# SCH_Stimulus-Shield-_GroeiAcademie-Frame.net
KiCad netlist of a schematic drawn in EasyEDA
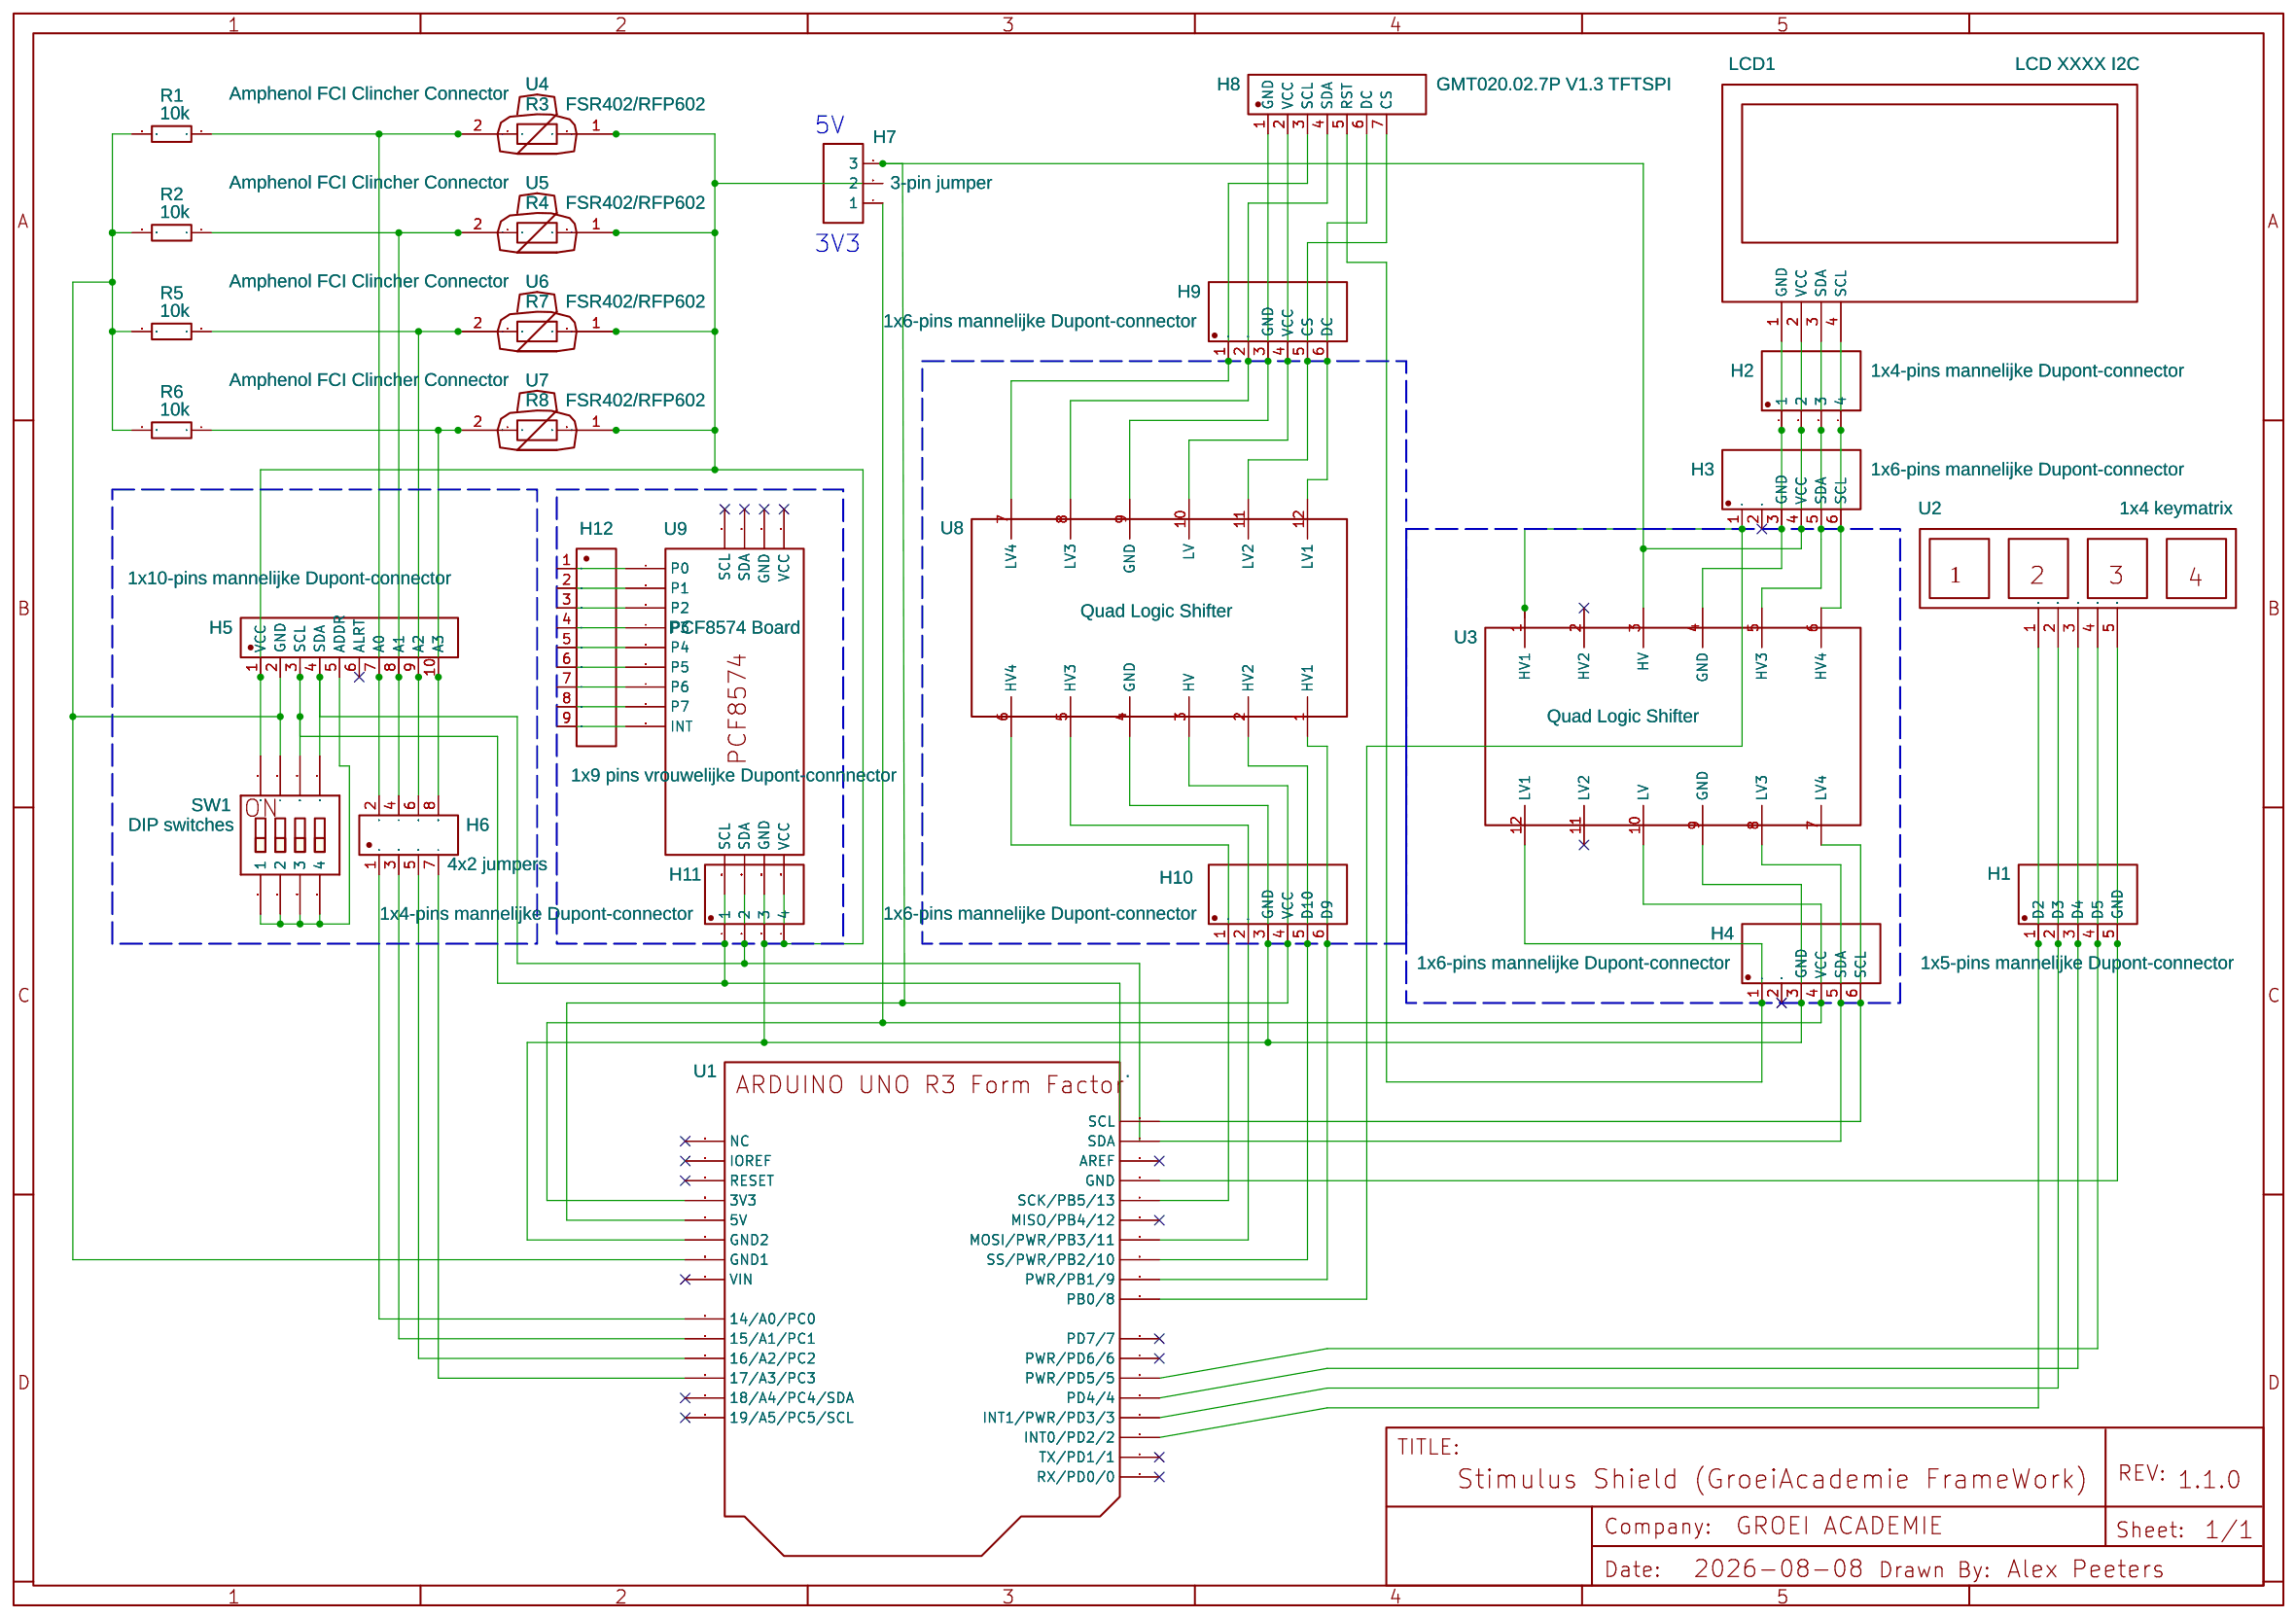
[diagram p0: schematic sheet]

(export (version "E")
  (design (tool "Eeschema 10.0.6"))
  (components
    (comp (ref "H1")
      (value "1x5-pins mannelijke Dupont-connector")
      (fields (field (name "Manufacturer Part") "B-2100S05P-A110") (field (name "Manufacturer") "Ckmtw(灿科盟)"))
      (libsource (lib "") (part "210S-1*5P L=11.6MMGold-plated black"))
    )
    (comp (ref "H2")
      (value "1x4-pins mannelijke Dupont-connector")
      (fields (field (name "Manufacturer Part") "B-2100S04P-A110") (field (name "Manufacturer") "Ckmtw(灿科盟)"))
      (libsource (lib "") (part "Header-Male-2.54_1x4"))
    )
    (comp (ref "H3")
      (value "1x6-pins mannelijke Dupont-connector")
      (fields (field (name "Manufacturer Part") "B-2100S06P-A110") (field (name "Manufacturer") "Ckmtw(灿科盟)"))
      (libsource (lib "") (part "210S-1*6P L=11.6MMGold-plated black"))
    )
    (comp (ref "H4")
      (value "1x6-pins mannelijke Dupont-connector")
      (fields (field (name "Manufacturer Part") "B-2100S06P-A110") (field (name "Manufacturer") "Ckmtw(灿科盟)"))
      (libsource (lib "") (part "210S-1*6P L=11.6MMGold-plated black"))
    )
    (comp (ref "H5")
      (value "1x10-pins mannelijke Dupont-connector")
      (fields (field (name "Manufacturer Part") "2.54-1*10") (field (name "Manufacturer") "ZHOURI(洲日)"))
      (libsource (lib "") (part "2.54-1*10"))
    )
    (comp (ref "H6")
      (value "4x2 jumpers")
      (fields (field (name "Manufacturer Part") "2.54-2*4P立贴针") (field (name "Manufacturer") "BOOMELE(博穆精密)"))
      (libsource (lib "") (part "2.54-2*4P立贴针"))
    )
    (comp (ref "H7") (value "3-pin jumper") (libsource (lib "") (part "HDR-F-2.54_1x3")))
    (comp (ref "H8")
      (value "GMT020.02.7P V1.3 TFTSPI")
      (fields (field (name "Manufacturer Part") "HDR-M-L12-3+4-1x8P-2.54"))
      (libsource (lib "") (part "PZ254R-11-08P"))
    )
    (comp (ref "H9")
      (value "1x6-pins mannelijke Dupont-connector")
      (fields (field (name "Manufacturer Part") "B-2100S06P-A110") (field (name "Manufacturer") "Ckmtw(灿科盟)"))
      (libsource (lib "") (part "210S-1*6P L=11.6MMGold-plated black_2"))
    )
    (comp (ref "H10")
      (value "1x6-pins mannelijke Dupont-connector")
      (fields (field (name "Manufacturer Part") "B-2100S06P-A110") (field (name "Manufacturer") "Ckmtw(灿科盟)"))
      (libsource (lib "") (part "210S-1*6P L=11.6MMGold-plated black_1"))
    )
    (comp (ref "H11")
      (value "1x4-pins mannelijke Dupont-connector")
      (fields (field (name "Manufacturer Part") "B-2100S04P-A110") (field (name "Manufacturer") "Ckmtw(灿科盟)"))
      (libsource (lib "") (part "Header-Male-2.54_1x4"))
    )
    (comp (ref "H12")
      (value "1x9 pins vrouwelijke Dupont-connnector")
      (fields
        (field (name "Manufacturer Part") "HX PM1.27-1x9P ZC H2.0")
        (field (name "Manufacturer") "hanxia(韩下)")
      )
      (libsource (lib "") (part "HX PM1.27-1X9P ZC H2.0"))
    )
    (comp (ref "LCD1") (value "LCD XXXX I2C") (libsource (lib "") (part "I2CLCD16X2_N")))
    (comp (ref "R1")
      (value "10k")
      (fields (field (name "Manufacturer") "Made in China"))
      (libsource (lib "") (part "330Ω (331) ±5%"))
    )
    (comp (ref "R2")
      (value "10k")
      (fields (field (name "Manufacturer") "Made in China"))
      (libsource (lib "") (part "330Ω (331) ±5%"))
    )
    (comp (ref "R3") (value "FSR402/RFP602") (libsource (lib "") (part "FSR402-OPCION1")))
    (comp (ref "R4") (value "FSR402/RFP602") (libsource (lib "") (part "FSR402-OPCION1")))
    (comp (ref "R5")
      (value "10k")
      (fields (field (name "Manufacturer") "Made in China"))
      (libsource (lib "") (part "330Ω (331) ±5%"))
    )
    (comp (ref "R6")
      (value "10k")
      (fields (field (name "Manufacturer") "Made in China"))
      (libsource (lib "") (part "330Ω (331) ±5%"))
    )
    (comp (ref "R7") (value "FSR402/RFP602") (libsource (lib "") (part "FSR402-OPCION1")))
    (comp (ref "R8") (value "FSR402/RFP602") (libsource (lib "") (part "FSR402-OPCION1")))
    (comp (ref "SW1")
      (value "DIP switches")
      (fields
        (field (name "Manufacturer Part") "DIP switch,Dip Switch,DSWB04LHGET")
        (field (name "Manufacturer") "KE")
      )
      (libsource (lib "") (part "DIP switch 4 Channel"))
    )
    (comp (ref "U1") (value ".") (libsource (lib "") (part "ARDUINO UNO r3")))
    (comp (ref "U2") (value "1x4 keymatrix") (libsource (lib "") (part "Клавиатура 4*4")))
    (comp (ref "U3") (value "Quad Logic Shifter") (libsource (lib "") (part "Quad Logic Shifter_1")))
    (comp (ref "U4")
      (value "Amphenol FCI Clincher Connector")
      (fields (field (name "Manufacturer Part") "AT04-2P-BM02") (field (name "Manufacturer") "Amphenol"))
      (libsource (lib "") (part "AT04-2P"))
    )
    (comp (ref "U5")
      (value "Amphenol FCI Clincher Connector")
      (fields (field (name "Manufacturer Part") "AT04-2P-BM02") (field (name "Manufacturer") "Amphenol"))
      (libsource (lib "") (part "AT04-2P"))
    )
    (comp (ref "U6")
      (value "Amphenol FCI Clincher Connector")
      (fields (field (name "Manufacturer Part") "AT04-2P-BM02") (field (name "Manufacturer") "Amphenol"))
      (libsource (lib "") (part "AT04-2P"))
    )
    (comp (ref "U7")
      (value "Amphenol FCI Clincher Connector")
      (fields (field (name "Manufacturer Part") "AT04-2P-BM02") (field (name "Manufacturer") "Amphenol"))
      (libsource (lib "") (part "AT04-2P"))
    )
    (comp (ref "U8") (value "Quad Logic Shifter") (libsource (lib "") (part "Quad Logic Shifter")))
    (comp (ref "U9")
      (value "PCF8574 Board")
      (fields
        (field (name "Manufacturer Part") "PCF8574 IO Expansion Board")
        (field (name "Manufacturer") "WaveShare")
      )
      (libsource (lib "") (part "PCF8574 IO Expansion Board"))
    )
  )
  (nets
    (net (code "1") (name "Net-(H1-D2)") (class "Default")
      (node (ref "H1") (pin "1") (pinfunction "D2_1") (pintype "unspecified"))
      (node (ref "U1") (pin "3") (pinfunction "INT0/PD2/2_3") (pintype "unspecified"))
      (node (ref "U2") (pin "1") (pinfunction "C1_1") (pintype "unspecified"))
    )
    (net (code "2") (name "Net-(H1-D3)") (class "Default")
      (node (ref "H1") (pin "2") (pinfunction "D3_2") (pintype "unspecified"))
      (node (ref "U1") (pin "4") (pinfunction "INT1/PWR/PD3/3_4") (pintype "unspecified"))
      (node (ref "U2") (pin "2") (pinfunction "C2_2") (pintype "unspecified"))
    )
    (net (code "3") (name "Net-(H1-D4)") (class "Default")
      (node (ref "H1") (pin "3") (pinfunction "D4_3") (pintype "unspecified"))
      (node (ref "U1") (pin "5") (pinfunction "PD4/4_5") (pintype "unspecified"))
      (node (ref "U2") (pin "3") (pinfunction "C3_3") (pintype "unspecified"))
    )
    (net (code "4") (name "Net-(H1-D5)") (class "Default")
      (node (ref "H1") (pin "4") (pinfunction "D5_4") (pintype "unspecified"))
      (node (ref "U1") (pin "6") (pinfunction "PWR/PD5/5_6") (pintype "unspecified"))
      (node (ref "U2") (pin "4") (pinfunction "R1_4") (pintype "unspecified"))
    )
    (net (code "5") (name "Net-(H1-GND)") (class "Default")
      (node (ref "H1") (pin "5") (pinfunction "GND_5") (pintype "unspecified"))
      (node (ref "U1") (pin "15") (pinfunction "GND_15") (pintype "passive"))
      (node (ref "U2") (pin "5") (pinfunction "R2_5") (pintype "unspecified"))
    )
    (net (code "6") (name "Net-(H3-GND)") (class "Default")
      (node (ref "H2") (pin "1") (pinfunction "1_1") (pintype "unspecified"))
      (node (ref "H3") (pin "3") (pinfunction "GND_3") (pintype "unspecified"))
      (node (ref "LCD1") (pin "1") (pinfunction "GND_1") (pintype "unspecified"))
      (node (ref "U3") (pin "4") (pinfunction "GND_4") (pintype "unspecified"))
    )
    (net (code "7") (name "Net-(H3-SCL)") (class "Default")
      (node (ref "H2") (pin "4") (pinfunction "4_4") (pintype "unspecified"))
      (node (ref "H3") (pin "6") (pinfunction "SCL_6") (pintype "unspecified"))
      (node (ref "LCD1") (pin "4") (pinfunction "SCL_4") (pintype "unspecified"))
      (node (ref "U3") (pin "6") (pinfunction "HV4_6") (pintype "unspecified"))
    )
    (net (code "8") (name "Net-(H3-SDA)") (class "Default")
      (node (ref "H2") (pin "3") (pinfunction "3_3") (pintype "unspecified"))
      (node (ref "H3") (pin "5") (pinfunction "SDA_5") (pintype "unspecified"))
      (node (ref "LCD1") (pin "3") (pinfunction "SDA_3") (pintype "unspecified"))
      (node (ref "U3") (pin "5") (pinfunction "HV3_5") (pintype "unspecified"))
    )
    (net (code "9") (name "Net-(H4-SCL)") (class "Default")
      (node (ref "H4") (pin "6") (pinfunction "SCL_6") (pintype "unspecified"))
      (node (ref "U1") (pin "18") (pinfunction "SCL_18") (pintype "unspecified"))
      (node (ref "U3") (pin "7") (pinfunction "LV4_7") (pintype "unspecified"))
    )
    (net (code "10") (name "Net-(H4-SDA)") (class "Default")
      (node (ref "H4") (pin "5") (pinfunction "SDA_5") (pintype "unspecified"))
      (node (ref "U1") (pin "17") (pinfunction "SDA_17") (pintype "unspecified"))
      (node (ref "U3") (pin "8") (pinfunction "LV3_8") (pintype "unspecified"))
    )
    (net (code "11") (name "Net-(H4-VCC)") (class "Default")
      (node (ref "H4") (pin "4") (pinfunction "VCC_4") (pintype "unspecified"))
      (node (ref "H7") (pin "1") (pinfunction "1_1") (pintype "input"))
      (node (ref "U1") (pin "29") (pinfunction "3V3_29") (pintype "passive"))
      (node (ref "U3") (pin "10") (pinfunction "LV_10") (pintype "unspecified"))
    )
    (net (code "12") (name "Net-(H5-A0)") (class "Default")
      (node (ref "H5") (pin "7") (pinfunction "A0_7") (pintype "unspecified"))
      (node (ref "H6") (pin "2") (pinfunction "2_2") (pintype "unspecified"))
      (node (ref "R1") (pin "1") (pinfunction "1_1") (pintype "unspecified"))
      (node (ref "R3") (pin "1") (pinfunction "1_1") (pintype "unspecified"))
      (node (ref "U4") (pin "2") (pinfunction "2_2") (pintype "unspecified"))
    )
    (net (code "13") (name "Net-(H5-A1)") (class "Default")
      (node (ref "H5") (pin "8") (pinfunction "A1_8") (pintype "unspecified"))
      (node (ref "H6") (pin "4") (pinfunction "4_4") (pintype "unspecified"))
      (node (ref "R2") (pin "1") (pinfunction "1_1") (pintype "unspecified"))
      (node (ref "R4") (pin "1") (pinfunction "1_1") (pintype "unspecified"))
      (node (ref "U5") (pin "2") (pinfunction "2_2") (pintype "unspecified"))
    )
    (net (code "14") (name "Net-(H5-A2)") (class "Default")
      (node (ref "H5") (pin "9") (pinfunction "A2_9") (pintype "unspecified"))
      (node (ref "H6") (pin "6") (pinfunction "6_6") (pintype "unspecified"))
      (node (ref "R5") (pin "1") (pinfunction "1_1") (pintype "unspecified"))
      (node (ref "R7") (pin "1") (pinfunction "1_1") (pintype "unspecified"))
      (node (ref "U6") (pin "2") (pinfunction "2_2") (pintype "unspecified"))
    )
    (net (code "15") (name "Net-(H5-A3)") (class "Default")
      (node (ref "H5") (pin "10") (pinfunction "A3_10") (pintype "unspecified"))
      (node (ref "H6") (pin "8") (pinfunction "8_8") (pintype "unspecified"))
      (node (ref "R6") (pin "1") (pinfunction "1_1") (pintype "unspecified"))
      (node (ref "R8") (pin "1") (pinfunction "1_1") (pintype "unspecified"))
      (node (ref "U7") (pin "2") (pinfunction "2_2") (pintype "unspecified"))
    )
    (net (code "16") (name "Net-(H5-ADDR)") (class "Default")
      (node (ref "H5") (pin "5") (pinfunction "ADDR_5") (pintype "unspecified"))
      (node (ref "SW1") (pin "1O") (pinfunction "1_1O") (pintype "input"))
      (node (ref "SW1") (pin "2O") (pinfunction "2_2O") (pintype "input"))
      (node (ref "SW1") (pin "3O") (pinfunction "3_3O") (pintype "input"))
      (node (ref "SW1") (pin "4O") (pinfunction "4_4O") (pintype "input"))
    )
    (net (code "17") (name "Net-(H5-GND)") (class "Default")
      (node (ref "H5") (pin "2") (pinfunction "GND_2") (pintype "unspecified"))
      (node (ref "R1") (pin "2") (pinfunction "2_2") (pintype "unspecified"))
      (node (ref "R2") (pin "2") (pinfunction "2_2") (pintype "unspecified"))
      (node (ref "R5") (pin "2") (pinfunction "2_2") (pintype "unspecified"))
      (node (ref "R6") (pin "2") (pinfunction "2_2") (pintype "unspecified"))
      (node (ref "SW1") (pin "2I") (pinfunction "7_2I") (pintype "input"))
      (node (ref "U1") (pin "26") (pinfunction "GND1_26") (pintype "passive"))
    )
    (net (code "18") (name "Net-(H5-SCL)") (class "Default")
      (node (ref "H11") (pin "1") (pinfunction "1_1") (pintype "unspecified"))
      (node (ref "H5") (pin "3") (pinfunction "SCL_3") (pintype "unspecified"))
      (node (ref "SW1") (pin "3I") (pinfunction "6_3I") (pintype "input"))
      (node (ref "U9") (pin "SCL") (pinfunction "SCL_SCL") (pintype "unspecified"))
    )
    (net (code "19") (name "Net-(H5-SDA)") (class "Default")
      (node (ref "H11") (pin "2") (pinfunction "2_2") (pintype "unspecified"))
      (node (ref "H5") (pin "4") (pinfunction "SDA_4") (pintype "unspecified"))
      (node (ref "SW1") (pin "4I") (pinfunction "5_4I") (pintype "input"))
      (node (ref "U9") (pin "SDA") (pinfunction "SDA_SDA") (pintype "unspecified"))
    )
    (net (code "20") (name "Net-(H5-VCC)") (class "Default")
      (node (ref "H11") (pin "4") (pinfunction "4_4") (pintype "unspecified"))
      (node (ref "H5") (pin "1") (pinfunction "VCC_1") (pintype "unspecified"))
      (node (ref "H7") (pin "2") (pinfunction "2_2") (pintype "input"))
      (node (ref "R3") (pin "2") (pinfunction "2_2") (pintype "unspecified"))
      (node (ref "R4") (pin "2") (pinfunction "2_2") (pintype "unspecified"))
      (node (ref "R7") (pin "2") (pinfunction "2_2") (pintype "unspecified"))
      (node (ref "R8") (pin "2") (pinfunction "2_2") (pintype "unspecified"))
      (node (ref "SW1") (pin "1I") (pinfunction "8_1I") (pintype "input"))
      (node (ref "U4") (pin "1") (pinfunction "1_1") (pintype "unspecified"))
      (node (ref "U5") (pin "1") (pinfunction "1_1") (pintype "unspecified"))
      (node (ref "U6") (pin "1") (pinfunction "1_1") (pintype "unspecified"))
      (node (ref "U7") (pin "1") (pinfunction "1_1") (pintype "unspecified"))
      (node (ref "U9") (pin "VCC") (pinfunction "VCC_VCC") (pintype "unspecified"))
    )
    (net (code "21") (name "Net-(H8-CS)") (class "Default")
      (node (ref "H8") (pin "7") (pinfunction "CS_7") (pintype "unspecified"))
      (node (ref "H9") (pin "5") (pinfunction "CS_5") (pintype "unspecified"))
      (node (ref "U8") (pin "11") (pinfunction "LV2_11") (pintype "unspecified"))
    )
    (net (code "22") (name "Net-(H8-DC)") (class "Default")
      (node (ref "H8") (pin "6") (pinfunction "DC_6") (pintype "unspecified"))
      (node (ref "H9") (pin "6") (pinfunction "DC_6") (pintype "unspecified"))
      (node (ref "U8") (pin "12") (pinfunction "LV1_12") (pintype "unspecified"))
    )
    (net (code "23") (name "Net-(H8-GND)") (class "Default")
      (node (ref "H8") (pin "1") (pinfunction "GND_1") (pintype "unspecified"))
      (node (ref "H9") (pin "3") (pinfunction "GND_3") (pintype "unspecified"))
      (node (ref "U8") (pin "9") (pinfunction "GND_9") (pintype "unspecified"))
    )
    (net (code "24") (name "Net-(H8-RST)") (class "Default")
      (node (ref "H4") (pin "1") (pinfunction "1_1") (pintype "unspecified"))
      (node (ref "H8") (pin "5") (pinfunction "RST_5") (pintype "unspecified"))
      (node (ref "U3") (pin "12") (pinfunction "LV1_12") (pintype "unspecified"))
    )
    (net (code "25") (name "Net-(H8-SCL)") (class "Default")
      (node (ref "H8") (pin "3") (pinfunction "SCL_3") (pintype "unspecified"))
      (node (ref "H9") (pin "1") (pinfunction "1_1") (pintype "unspecified"))
      (node (ref "U8") (pin "7") (pinfunction "LV4_7") (pintype "unspecified"))
    )
    (net (code "26") (name "Net-(H8-SDA)") (class "Default")
      (node (ref "H8") (pin "4") (pinfunction "SDA_4") (pintype "unspecified"))
      (node (ref "H9") (pin "2") (pinfunction "2_2") (pintype "unspecified"))
      (node (ref "U8") (pin "8") (pinfunction "LV3_8") (pintype "unspecified"))
    )
    (net (code "27") (name "Net-(H8-VCC)") (class "Default")
      (node (ref "H8") (pin "2") (pinfunction "VCC_2") (pintype "unspecified"))
      (node (ref "H9") (pin "4") (pinfunction "VCC_4") (pintype "unspecified"))
      (node (ref "U8") (pin "10") (pinfunction "LV_10") (pintype "unspecified"))
    )
    (net (code "28") (name "Net-(H10-D9)") (class "Default")
      (node (ref "H10") (pin "6") (pinfunction "D9_6") (pintype "unspecified"))
      (node (ref "U1") (pin "10") (pinfunction "PWR/PB1/9_10") (pintype "unspecified"))
      (node (ref "U8") (pin "1") (pinfunction "HV1_1") (pintype "unspecified"))
    )
    (net (code "29") (name "Net-(H10-D10)") (class "Default")
      (node (ref "H10") (pin "5") (pinfunction "D10_5") (pintype "unspecified"))
      (node (ref "U1") (pin "11") (pinfunction "SS/PWR/PB2/10_11") (pintype "unspecified"))
      (node (ref "U8") (pin "2") (pinfunction "HV2_2") (pintype "unspecified"))
    )
    (net (code "30") (name "Net-(H10-GND)") (class "Default")
      (node (ref "H10") (pin "3") (pinfunction "GND_3") (pintype "unspecified"))
      (node (ref "H11") (pin "3") (pinfunction "3_3") (pintype "unspecified"))
      (node (ref "H4") (pin "3") (pinfunction "GND_3") (pintype "unspecified"))
      (node (ref "U1") (pin "27") (pinfunction "GND2_27") (pintype "passive"))
      (node (ref "U3") (pin "9") (pinfunction "GND_9") (pintype "unspecified"))
      (node (ref "U8") (pin "4") (pinfunction "GND_4") (pintype "unspecified"))
      (node (ref "U9") (pin "GND") (pinfunction "GND_GND") (pintype "unspecified"))
    )
    (net (code "31") (name "Net-(H10-VCC)") (class "Default")
      (node (ref "H10") (pin "4") (pinfunction "VCC_4") (pintype "unspecified"))
      (node (ref "H2") (pin "2") (pinfunction "2_2") (pintype "unspecified"))
      (node (ref "H3") (pin "4") (pinfunction "VCC_4") (pintype "unspecified"))
      (node (ref "H7") (pin "3") (pinfunction "3_3") (pintype "input"))
      (node (ref "LCD1") (pin "2") (pinfunction "VCC_2") (pintype "unspecified"))
      (node (ref "U1") (pin "28") (pinfunction "5V_28") (pintype "passive"))
      (node (ref "U3") (pin "3") (pinfunction "HV_3") (pintype "unspecified"))
      (node (ref "U8") (pin "3") (pinfunction "HV_3") (pintype "unspecified"))
    )
    (net (code "32") (name "Net-(U1-14{slash}A0{slash}PC0)") (class "Default")
      (node (ref "H6") (pin "1") (pinfunction "1_1") (pintype "unspecified"))
      (node (ref "U1") (pin "24") (pinfunction "14/A0/PC0_24") (pintype "unspecified"))
    )
    (net (code "33") (name "Net-(U1-15{slash}A1{slash}PC1)") (class "Default")
      (node (ref "H6") (pin "3") (pinfunction "3_3") (pintype "unspecified"))
      (node (ref "U1") (pin "23") (pinfunction "15/A1/PC1_23") (pintype "unspecified"))
    )
    (net (code "34") (name "Net-(U1-16{slash}A2{slash}PC2)") (class "Default")
      (node (ref "H6") (pin "5") (pinfunction "5_5") (pintype "unspecified"))
      (node (ref "U1") (pin "22") (pinfunction "16/A2/PC2_22") (pintype "unspecified"))
    )
    (net (code "35") (name "Net-(U1-17{slash}A3{slash}PC3)") (class "Default")
      (node (ref "H6") (pin "7") (pinfunction "7_7") (pintype "unspecified"))
      (node (ref "U1") (pin "21") (pinfunction "17/A3/PC3_21") (pintype "unspecified"))
    )
    (net (code "36") (name "Net-(U1-MOSI{slash}PWR{slash}PB3{slash}11)") (class "Default")
      (node (ref "H10") (pin "2") (pinfunction "2_2") (pintype "unspecified"))
      (node (ref "U1") (pin "12") (pinfunction "MOSI/PWR/PB3/11_12") (pintype "unspecified"))
    )
    (net (code "37") (name "Net-(U1-PB0{slash}8)") (class "Default")
      (node (ref "H3") (pin "1") (pinfunction "1_1") (pintype "unspecified"))
      (node (ref "U1") (pin "9") (pinfunction "PB0/8_9") (pintype "unspecified"))
      (node (ref "U3") (pin "1") (pinfunction "HV1_1") (pintype "unspecified"))
    )
    (net (code "38") (name "Net-(U1-SCK{slash}PB5{slash}13)") (class "Default")
      (node (ref "H10") (pin "1") (pinfunction "1_1") (pintype "unspecified"))
      (node (ref "U1") (pin "14") (pinfunction "SCK/PB5/13_14") (pintype "unspecified"))
    )
    (net (code "39") (name "Net-(U9-INT)") (class "Default")
      (node (ref "H12") (pin "9") (pinfunction "9_9") (pintype "unspecified"))
      (node (ref "U9") (pin "9") (pinfunction "INT_9") (pintype "unspecified"))
    )
    (net (code "40") (name "Net-(U9-P0)") (class "Default")
      (node (ref "H12") (pin "1") (pinfunction "1_1") (pintype "unspecified"))
      (node (ref "U9") (pin "1") (pinfunction "P0_1") (pintype "unspecified"))
    )
    (net (code "41") (name "Net-(U9-P1)") (class "Default")
      (node (ref "H12") (pin "2") (pinfunction "2_2") (pintype "unspecified"))
      (node (ref "U9") (pin "2") (pinfunction "P1_2") (pintype "unspecified"))
    )
    (net (code "42") (name "Net-(U9-P2)") (class "Default")
      (node (ref "H12") (pin "3") (pinfunction "3_3") (pintype "unspecified"))
      (node (ref "U9") (pin "3") (pinfunction "P2_3") (pintype "unspecified"))
    )
    (net (code "43") (name "Net-(U9-P3)") (class "Default")
      (node (ref "H12") (pin "4") (pinfunction "4_4") (pintype "unspecified"))
      (node (ref "U9") (pin "4") (pinfunction "P3_4") (pintype "unspecified"))
    )
    (net (code "44") (name "Net-(U9-P4)") (class "Default")
      (node (ref "H12") (pin "5") (pinfunction "5_5") (pintype "unspecified"))
      (node (ref "U9") (pin "5") (pinfunction "P4_5") (pintype "unspecified"))
    )
    (net (code "45") (name "Net-(U9-P5)") (class "Default")
      (node (ref "H12") (pin "6") (pinfunction "6_6") (pintype "unspecified"))
      (node (ref "U9") (pin "6") (pinfunction "P5_6") (pintype "unspecified"))
    )
    (net (code "46") (name "Net-(U9-P6)") (class "Default")
      (node (ref "H12") (pin "7") (pinfunction "7_7") (pintype "unspecified"))
      (node (ref "U9") (pin "7") (pinfunction "P6_7") (pintype "unspecified"))
    )
    (net (code "47") (name "Net-(U9-P7)") (class "Default")
      (node (ref "H12") (pin "8") (pinfunction "8_8") (pintype "unspecified"))
      (node (ref "U9") (pin "8") (pinfunction "P7_8") (pintype "unspecified"))
    )
    (net (code "48") (name "unconnected-(H3-Pad2)") (class "Default")
      (node (ref "H3") (pin "2") (pinfunction "2_2") (pintype "unspecified+no_connect"))
    )
    (net (code "49") (name "unconnected-(H4-Pad2)") (class "Default")
      (node (ref "H4") (pin "2") (pinfunction "2_2") (pintype "unspecified+no_connect"))
    )
    (net (code "50") (name "unconnected-(H5-ALRT-Pad6)") (class "Default")
      (node (ref "H5") (pin "6") (pinfunction "ALRT_6") (pintype "unspecified+no_connect"))
    )
    (net (code "51") (name "unconnected-(U1-18{slash}A4{slash}PC4{slash}SDA-Pad20)") (class "Default")
      (node (ref "U1") (pin "20") (pinfunction "18/A4/PC4/SDA_20") (pintype "unspecified+no_connect"))
    )
    (net (code "52") (name "unconnected-(U1-19{slash}A5{slash}PC5{slash}SCL-Pad19)") (class "Default")
      (node (ref "U1") (pin "19") (pinfunction "19/A5/PC5/SCL_19") (pintype "unspecified+no_connect"))
    )
    (net (code "53") (name "unconnected-(U1-AREF-Pad16)") (class "Default")
      (node (ref "U1") (pin "16") (pinfunction "AREF_16") (pintype "unspecified+no_connect"))
    )
    (net (code "54") (name "unconnected-(U1-IOREF-Pad31)") (class "Default")
      (node (ref "U1") (pin "31") (pinfunction "IOREF_31") (pintype "unspecified+no_connect"))
    )
    (net (code "55") (name "unconnected-(U1-MISO{slash}PB4{slash}12-Pad13)") (class "Default")
      (node (ref "U1") (pin "13") (pinfunction "MISO/PB4/12_13") (pintype "unspecified+no_connect"))
    )
    (net (code "56") (name "unconnected-(U1-NC-Pad32)") (class "Default")
      (node (ref "U1") (pin "32") (pinfunction "NC_32") (pintype "unspecified+no_connect"))
    )
    (net (code "57") (name "unconnected-(U1-PD7{slash}7-Pad8)") (class "Default")
      (node (ref "U1") (pin "8") (pinfunction "PD7/7_8") (pintype "unspecified+no_connect"))
    )
    (net (code "58") (name "unconnected-(U1-PWR{slash}PD6{slash}6-Pad7)") (class "Default")
      (node (ref "U1") (pin "7") (pinfunction "PWR/PD6/6_7") (pintype "unspecified+no_connect"))
    )
    (net (code "59") (name "unconnected-(U1-RESET-Pad30)") (class "Default")
      (node (ref "U1") (pin "30") (pinfunction "RESET_30") (pintype "unspecified+no_connect"))
    )
    (net (code "60") (name "unconnected-(U1-RX{slash}PD0{slash}0-Pad1)") (class "Default")
      (node (ref "U1") (pin "1") (pinfunction "RX/PD0/0_1") (pintype "unspecified+no_connect"))
    )
    (net (code "61") (name "unconnected-(U1-TX{slash}PD1{slash}1-Pad2)") (class "Default")
      (node (ref "U1") (pin "2") (pinfunction "TX/PD1/1_2") (pintype "unspecified+no_connect"))
    )
    (net (code "62") (name "unconnected-(U1-VIN-Pad25)") (class "Default")
      (node (ref "U1") (pin "25") (pinfunction "VIN_25") (pintype "passive+no_connect"))
    )
    (net (code "63") (name "unconnected-(U3-HV2-Pad2)") (class "Default")
      (node (ref "U3") (pin "2") (pinfunction "HV2_2") (pintype "unspecified+no_connect"))
    )
    (net (code "64") (name "unconnected-(U3-LV2-Pad11)") (class "Default")
      (node (ref "U3") (pin "11") (pinfunction "LV2_11") (pintype "unspecified+no_connect"))
    )
    (net (code "65") (name "unconnected-(U8-HV3-Pad5)") (class "Default")
      (node (ref "U8") (pin "5") (pinfunction "HV3_5") (pintype "unspecified"))
    )
    (net (code "66") (name "unconnected-(U8-HV4-Pad6)") (class "Default")
      (node (ref "U8") (pin "6") (pinfunction "HV4_6") (pintype "unspecified"))
    )
    (net (code "67") (name "unconnected-(U9-GND-Pad12)") (class "Default")
      (node (ref "U9") (pin "12") (pinfunction "GND_12") (pintype "unspecified+no_connect"))
    )
    (net (code "68") (name "unconnected-(U9-SCL-Pad10)") (class "Default")
      (node (ref "U9") (pin "10") (pinfunction "SCL_10") (pintype "unspecified+no_connect"))
    )
    (net (code "69") (name "unconnected-(U9-SDA-Pad11)") (class "Default")
      (node (ref "U9") (pin "11") (pinfunction "SDA_11") (pintype "unspecified+no_connect"))
    )
    (net (code "70") (name "unconnected-(U9-VCC-Pad13)") (class "Default")
      (node (ref "U9") (pin "13") (pinfunction "VCC_13") (pintype "unspecified+no_connect"))
    )
  )
)
